# SensorManagementSystem.net
KiCad netlist of a schematic drawn in Altium Designer
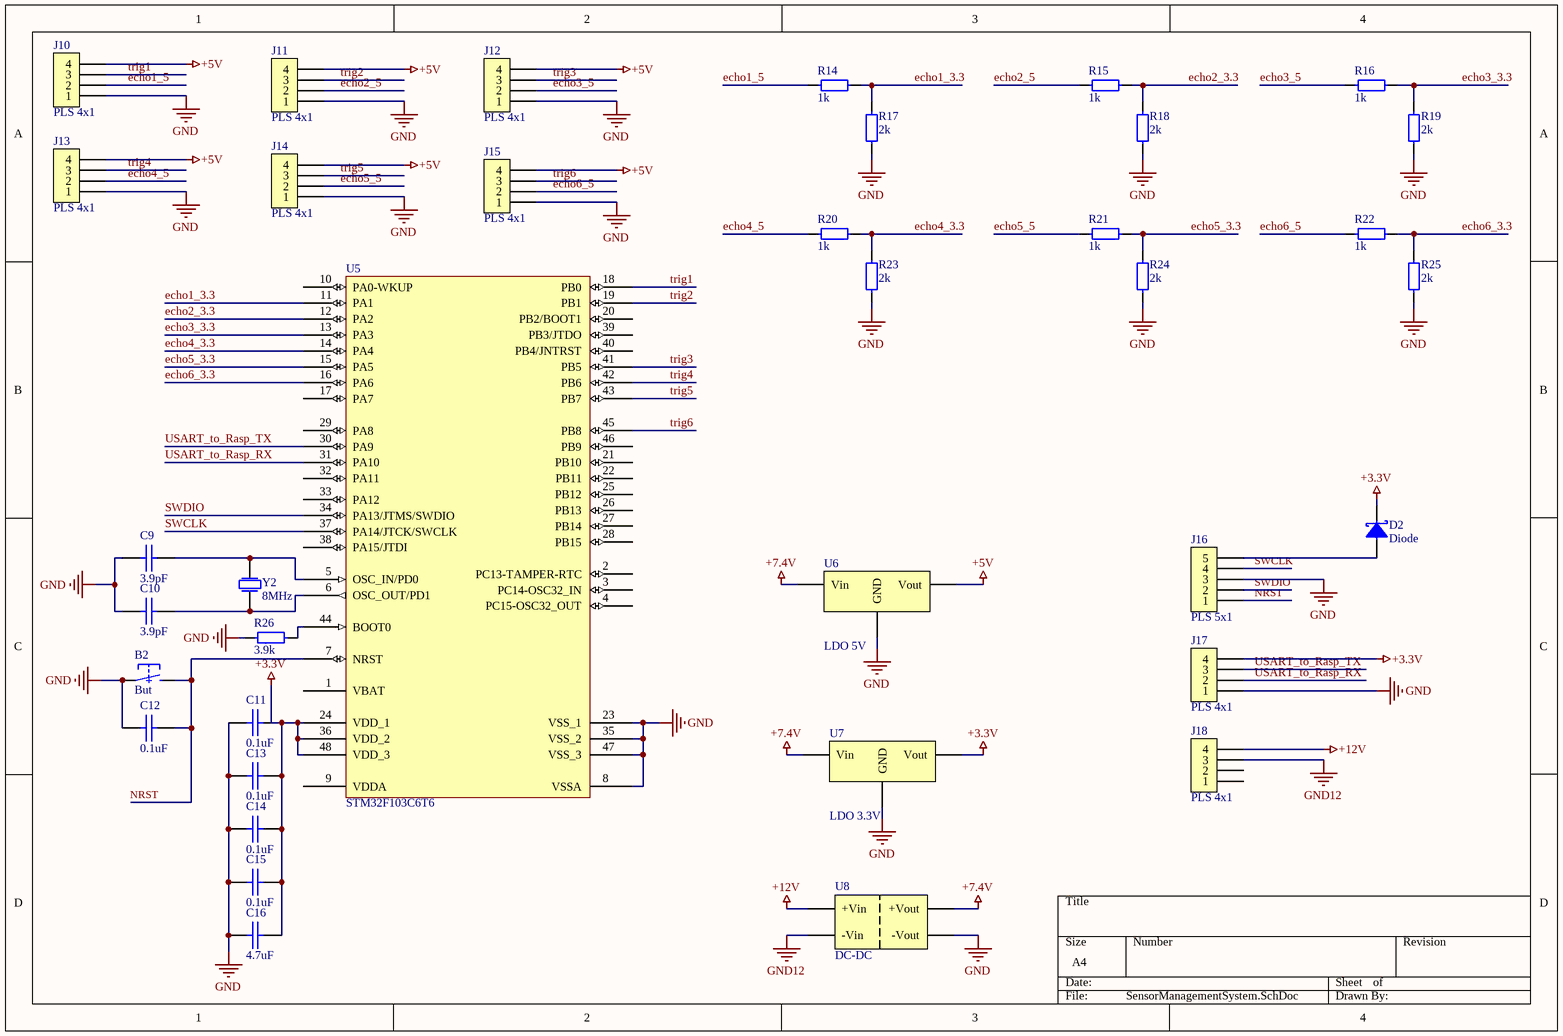
[diagram p0: SensorManagementSystem.SchDoc]

(export (version "E")
  (design (tool "Eeschema 10.0.6"))
  (components
    (comp (ref "B2")
      (value "But")
      (footprint "BUTTON 6x3.5")
      (description "Button 2 Conn SMD")
      (libsource (lib "RoboCor") (part "Button"))
    )
    (comp (ref "C9")
      (value "3.9pF")
      (footprint "0805 Capicator")
      (libsource (lib "RoboCor") (part "Cap 39pF"))
    )
    (comp (ref "C10")
      (value "3.9pF")
      (footprint "0805 Capicator")
      (libsource (lib "RoboCor") (part "Cap 39pF"))
    )
    (comp (ref "C11")
      (value "0.1uF")
      (footprint "0805 Capicator")
      (libsource (lib "RoboCor") (part "Cap 0.1uF"))
    )
    (comp (ref "C12")
      (value "0.1uF")
      (footprint "0805 Capicator")
      (libsource (lib "RoboCor") (part "Cap 0.1uF"))
    )
    (comp (ref "C13")
      (value "0.1uF")
      (footprint "0805 Capicator")
      (libsource (lib "RoboCor") (part "Cap 0.1uF"))
    )
    (comp (ref "C14")
      (value "0.1uF")
      (footprint "0805 Capicator")
      (libsource (lib "RoboCor") (part "Cap 0.1uF"))
    )
    (comp (ref "C15")
      (value "0.1uF")
      (footprint "0805 Capicator")
      (libsource (lib "RoboCor") (part "Cap 0.1uF"))
    )
    (comp (ref "C16")
      (value "4.7uF")
      (footprint "0805 Capicator")
      (libsource (lib "RoboCor") (part "Cap 4.7uF"))
    )
    (comp (ref "D2")
      (value "Diode")
      (footprint "sod-123")
      (description "0.5 A, Low Forward Voltage less than 385 mV, 400 mW Power Dissipation Package")
      (libsource (lib "RoboCor") (part "Diode Schottky"))
    )
    (comp (ref "J10")
      (value "PLS 4x1")
      (footprint "PLS 4x1")
      (description "Header, 4-Pin")
      (libsource (lib "RoboCor") (part "Conn 4"))
    )
    (comp (ref "J11")
      (value "PLS 4x1")
      (footprint "PLS 4x1")
      (description "Header, 4-Pin")
      (libsource (lib "RoboCor") (part "Conn 4"))
    )
    (comp (ref "J12")
      (value "PLS 4x1")
      (footprint "PLS 4x1")
      (description "Header, 4-Pin")
      (libsource (lib "RoboCor") (part "Conn 4"))
    )
    (comp (ref "J13")
      (value "PLS 4x1")
      (footprint "PLS 4x1")
      (description "Header, 4-Pin")
      (libsource (lib "RoboCor") (part "Conn 4"))
    )
    (comp (ref "J14")
      (value "PLS 4x1")
      (footprint "PLS 4x1")
      (description "Header, 4-Pin")
      (libsource (lib "RoboCor") (part "Conn 4"))
    )
    (comp (ref "J15")
      (value "PLS 4x1")
      (footprint "PLS 4x1")
      (description "Header, 4-Pin")
      (libsource (lib "RoboCor") (part "Conn 4"))
    )
    (comp (ref "J16")
      (value "PLS 5x1")
      (footprint "PLS 5x1")
      (description "Header, 5-Pin")
      (libsource (lib "RoboCor") (part "Conn 5"))
    )
    (comp (ref "J17")
      (value "PLS 4x1")
      (footprint "PLS 4x1")
      (description "Header, 4-Pin")
      (libsource (lib "RoboCor") (part "Conn 4"))
    )
    (comp (ref "J18")
      (value "PLS 4x1")
      (footprint "PLS 4x1")
      (description "Header, 4-Pin")
      (libsource (lib "RoboCor") (part "Conn 4"))
    )
    (comp (ref "R14") (value "1k") (footprint "0805 Resistor") (libsource (lib "RoboCor") (part "Res 1k")))
    (comp (ref "R15") (value "1k") (footprint "0805 Resistor") (libsource (lib "RoboCor") (part "Res 1k")))
    (comp (ref "R16") (value "1k") (footprint "0805 Resistor") (libsource (lib "RoboCor") (part "Res 1k")))
    (comp (ref "R17") (value "2k") (footprint "0805 Resistor") (libsource (lib "RoboCor") (part "Res 2k")))
    (comp (ref "R18") (value "2k") (footprint "0805 Resistor") (libsource (lib "RoboCor") (part "Res 2k")))
    (comp (ref "R19") (value "2k") (footprint "0805 Resistor") (libsource (lib "RoboCor") (part "Res 2k")))
    (comp (ref "R20") (value "1k") (footprint "0805 Resistor") (libsource (lib "RoboCor") (part "Res 1k")))
    (comp (ref "R21") (value "1k") (footprint "0805 Resistor") (libsource (lib "RoboCor") (part "Res 1k")))
    (comp (ref "R22") (value "1k") (footprint "0805 Resistor") (libsource (lib "RoboCor") (part "Res 1k")))
    (comp (ref "R23") (value "2k") (footprint "0805 Resistor") (libsource (lib "RoboCor") (part "Res 2k")))
    (comp (ref "R24") (value "2k") (footprint "0805 Resistor") (libsource (lib "RoboCor") (part "Res 2k")))
    (comp (ref "R25") (value "2k") (footprint "0805 Resistor") (libsource (lib "RoboCor") (part "Res 2k")))
    (comp (ref "R26")
      (value "3.9k")
      (footprint "0805 Resistor")
      (libsource (lib "RoboCor") (part "Res 3.9k"))
    )
    (comp (ref "U5")
      (value "STM32F103C6T6")
      (footprint "STM32F103C6T6")
      (libsource (lib "RoboCor") (part "STM32F103C6T6"))
    )
    (comp (ref "U6")
      (value "LDO 5V")
      (footprint "TO-252")
      (description "LDO Regulator Pos 5V 1A")
      (libsource (lib "RoboCor") (part "LDO 5V"))
    )
    (comp (ref "U7")
      (value "LDO 3.3V")
      (footprint "SOT-223")
      (description "LDO Regulator Pos 3.3V 1.3A 4-Pin(3+Tab) SOT-223 T/R")
      (libsource (lib "RoboCor") (part "LDO 3.3V"))
    )
    (comp (ref "U8") (value "DC-DC") (footprint "DC-DC") (libsource (lib "RoboCor") (part "DC-DC")))
    (comp (ref "Y2")
      (value "8MHz")
      (footprint "hc-49sm")
      (description "Crystal. HC-49SM (US)")
      (libsource (lib "RoboCor") (part "Crystal 8MHz"))
    )
  )
  (nets
    (net (code "1") (name "+3.3V") (class "Default")
      (node (ref "C11") (pin "2") (pinfunction "2_2") (pintype "passive"))
      (node (ref "C13") (pin "2") (pinfunction "2_2") (pintype "passive"))
      (node (ref "C14") (pin "2") (pinfunction "2_2") (pintype "passive"))
      (node (ref "C15") (pin "2") (pinfunction "2_2") (pintype "passive"))
      (node (ref "C16") (pin "2") (pinfunction "2_2") (pintype "passive"))
      (node (ref "D2") (pin "2") (pinfunction "2_2") (pintype "passive"))
      (node (ref "J17") (pin "4") (pinfunction "4_4") (pintype "passive"))
      (node (ref "U5") (pin "24") (pinfunction "VDD_1_24") (pintype "power_in"))
      (node (ref "U5") (pin "36") (pinfunction "VDD_2_36") (pintype "power_in"))
      (node (ref "U5") (pin "48") (pinfunction "VDD_3_48") (pintype "power_in"))
      (node (ref "U7") (pin "2") (pinfunction "Vout_2") (pintype "power_in"))
    )
    (net (code "2") (name "+5V") (class "Default")
      (node (ref "J10") (pin "4") (pinfunction "4_4") (pintype "passive"))
      (node (ref "J11") (pin "4") (pinfunction "4_4") (pintype "passive"))
      (node (ref "J12") (pin "4") (pinfunction "4_4") (pintype "passive"))
      (node (ref "J13") (pin "4") (pinfunction "4_4") (pintype "passive"))
      (node (ref "J14") (pin "4") (pinfunction "4_4") (pintype "passive"))
      (node (ref "J15") (pin "4") (pinfunction "4_4") (pintype "passive"))
      (node (ref "U6") (pin "2") (pinfunction "Vout_2") (pintype "power_in"))
    )
    (net (code "3") (name "+7.4V") (class "Default")
      (node (ref "U6") (pin "3") (pinfunction "Vin_3") (pintype "power_in"))
      (node (ref "U7") (pin "3") (pinfunction "Vin_3") (pintype "power_in"))
      (node (ref "U8") (pin "3") (pinfunction "+Vout_3") (pintype "power_in"))
    )
    (net (code "4") (name "+12V") (class "Default")
      (node (ref "J18") (pin "4") (pinfunction "4_4") (pintype "passive"))
      (node (ref "U8") (pin "1") (pinfunction "+Vin_1") (pintype "power_in"))
    )
    (net (code "5") (name "/NRST") (class "Default")
      (node (ref "B2") (pin "2") (pinfunction "2_2") (pintype "passive"))
      (node (ref "C12") (pin "2") (pinfunction "2_2") (pintype "passive"))
      (node (ref "J16") (pin "1") (pinfunction "1_1") (pintype "passive"))
      (node (ref "U5") (pin "7") (pinfunction "NRST_7") (pintype "bidirectional"))
    )
    (net (code "6") (name "/SWCLK") (class "Default")
      (node (ref "J16") (pin "4") (pinfunction "4_4") (pintype "passive"))
      (node (ref "U5") (pin "37") (pinfunction "PA14/JTCK/SWCLK_37") (pintype "bidirectional"))
    )
    (net (code "7") (name "/SWDIO") (class "Default")
      (node (ref "J16") (pin "2") (pinfunction "2_2") (pintype "passive"))
      (node (ref "U5") (pin "34") (pinfunction "PA13/JTMS/SWDIO_34") (pintype "bidirectional"))
    )
    (net (code "8") (name "/USART_to_Rasp_RX") (class "Default")
      (node (ref "J17") (pin "2") (pinfunction "2_2") (pintype "passive"))
      (node (ref "U5") (pin "31") (pinfunction "PA10_31") (pintype "bidirectional"))
    )
    (net (code "9") (name "/USART_to_Rasp_TX") (class "Default")
      (node (ref "J17") (pin "3") (pinfunction "3_3") (pintype "passive"))
      (node (ref "U5") (pin "30") (pinfunction "PA9_30") (pintype "bidirectional"))
    )
    (net (code "10") (name "/echo1_3.3") (class "Default")
      (node (ref "R14") (pin "2") (pinfunction "2_2") (pintype "passive"))
      (node (ref "R17") (pin "2") (pinfunction "2_2") (pintype "passive"))
      (node (ref "U5") (pin "11") (pinfunction "PA1_11") (pintype "bidirectional"))
    )
    (net (code "11") (name "/echo1_5") (class "Default")
      (node (ref "J10") (pin "2") (pinfunction "2_2") (pintype "passive"))
      (node (ref "R14") (pin "1") (pinfunction "1_1") (pintype "passive"))
    )
    (net (code "12") (name "/echo2_3.3") (class "Default")
      (node (ref "R15") (pin "2") (pinfunction "2_2") (pintype "passive"))
      (node (ref "R18") (pin "2") (pinfunction "2_2") (pintype "passive"))
      (node (ref "U5") (pin "12") (pinfunction "PA2_12") (pintype "bidirectional"))
    )
    (net (code "13") (name "/echo2_5") (class "Default")
      (node (ref "J11") (pin "2") (pinfunction "2_2") (pintype "passive"))
      (node (ref "R15") (pin "1") (pinfunction "1_1") (pintype "passive"))
    )
    (net (code "14") (name "/echo3_3.3") (class "Default")
      (node (ref "R16") (pin "2") (pinfunction "2_2") (pintype "passive"))
      (node (ref "R19") (pin "2") (pinfunction "2_2") (pintype "passive"))
      (node (ref "U5") (pin "13") (pinfunction "PA3_13") (pintype "bidirectional"))
    )
    (net (code "15") (name "/echo3_5") (class "Default")
      (node (ref "J12") (pin "2") (pinfunction "2_2") (pintype "passive"))
      (node (ref "R16") (pin "1") (pinfunction "1_1") (pintype "passive"))
    )
    (net (code "16") (name "/echo4_3.3") (class "Default")
      (node (ref "R20") (pin "2") (pinfunction "2_2") (pintype "passive"))
      (node (ref "R23") (pin "2") (pinfunction "2_2") (pintype "passive"))
      (node (ref "U5") (pin "14") (pinfunction "PA4_14") (pintype "bidirectional"))
    )
    (net (code "17") (name "/echo4_5") (class "Default")
      (node (ref "J13") (pin "2") (pinfunction "2_2") (pintype "passive"))
      (node (ref "R20") (pin "1") (pinfunction "1_1") (pintype "passive"))
    )
    (net (code "18") (name "/echo5_3.3") (class "Default")
      (node (ref "R21") (pin "2") (pinfunction "2_2") (pintype "passive"))
      (node (ref "R24") (pin "2") (pinfunction "2_2") (pintype "passive"))
      (node (ref "U5") (pin "15") (pinfunction "PA5_15") (pintype "bidirectional"))
    )
    (net (code "19") (name "/echo5_5") (class "Default")
      (node (ref "J14") (pin "2") (pinfunction "2_2") (pintype "passive"))
      (node (ref "R21") (pin "1") (pinfunction "1_1") (pintype "passive"))
    )
    (net (code "20") (name "/echo6_3.3") (class "Default")
      (node (ref "R22") (pin "2") (pinfunction "2_2") (pintype "passive"))
      (node (ref "R25") (pin "2") (pinfunction "2_2") (pintype "passive"))
      (node (ref "U5") (pin "16") (pinfunction "PA6_16") (pintype "bidirectional"))
    )
    (net (code "21") (name "/echo6_5") (class "Default")
      (node (ref "J15") (pin "2") (pinfunction "2_2") (pintype "passive"))
      (node (ref "R22") (pin "1") (pinfunction "1_1") (pintype "passive"))
    )
    (net (code "22") (name "/trig1") (class "Default")
      (node (ref "J10") (pin "3") (pinfunction "3_3") (pintype "passive"))
      (node (ref "U5") (pin "18") (pinfunction "PB0_18") (pintype "bidirectional"))
    )
    (net (code "23") (name "/trig2") (class "Default")
      (node (ref "J11") (pin "3") (pinfunction "3_3") (pintype "passive"))
      (node (ref "U5") (pin "19") (pinfunction "PB1_19") (pintype "bidirectional"))
    )
    (net (code "24") (name "/trig3") (class "Default")
      (node (ref "J12") (pin "3") (pinfunction "3_3") (pintype "passive"))
      (node (ref "U5") (pin "41") (pinfunction "PB5_41") (pintype "bidirectional"))
    )
    (net (code "25") (name "/trig4") (class "Default")
      (node (ref "J13") (pin "3") (pinfunction "3_3") (pintype "passive"))
      (node (ref "U5") (pin "42") (pinfunction "PB6_42") (pintype "bidirectional"))
    )
    (net (code "26") (name "/trig5") (class "Default")
      (node (ref "J14") (pin "3") (pinfunction "3_3") (pintype "passive"))
      (node (ref "U5") (pin "43") (pinfunction "PB7_43") (pintype "bidirectional"))
    )
    (net (code "27") (name "/trig6") (class "Default")
      (node (ref "J15") (pin "3") (pinfunction "3_3") (pintype "passive"))
      (node (ref "U5") (pin "45") (pinfunction "PB8_45") (pintype "bidirectional"))
    )
    (net (code "28") (name "GND") (class "Default")
      (node (ref "B2") (pin "1") (pinfunction "1_1") (pintype "passive"))
      (node (ref "C10") (pin "1") (pinfunction "1_1") (pintype "passive"))
      (node (ref "C11") (pin "1") (pinfunction "1_1") (pintype "passive"))
      (node (ref "C12") (pin "1") (pinfunction "1_1") (pintype "passive"))
      (node (ref "C13") (pin "1") (pinfunction "1_1") (pintype "passive"))
      (node (ref "C14") (pin "1") (pinfunction "1_1") (pintype "passive"))
      (node (ref "C15") (pin "1") (pinfunction "1_1") (pintype "passive"))
      (node (ref "C16") (pin "1") (pinfunction "1_1") (pintype "passive"))
      (node (ref "C9") (pin "1") (pinfunction "1_1") (pintype "passive"))
      (node (ref "J10") (pin "1") (pinfunction "1_1") (pintype "passive"))
      (node (ref "J11") (pin "1") (pinfunction "1_1") (pintype "passive"))
      (node (ref "J12") (pin "1") (pinfunction "1_1") (pintype "passive"))
      (node (ref "J13") (pin "1") (pinfunction "1_1") (pintype "passive"))
      (node (ref "J14") (pin "1") (pinfunction "1_1") (pintype "passive"))
      (node (ref "J15") (pin "1") (pinfunction "1_1") (pintype "passive"))
      (node (ref "J16") (pin "3") (pinfunction "3_3") (pintype "passive"))
      (node (ref "J17") (pin "1") (pinfunction "1_1") (pintype "passive"))
      (node (ref "R17") (pin "1") (pinfunction "1_1") (pintype "passive"))
      (node (ref "R18") (pin "1") (pinfunction "1_1") (pintype "passive"))
      (node (ref "R19") (pin "1") (pinfunction "1_1") (pintype "passive"))
      (node (ref "R23") (pin "1") (pinfunction "1_1") (pintype "passive"))
      (node (ref "R24") (pin "1") (pinfunction "1_1") (pintype "passive"))
      (node (ref "R25") (pin "1") (pinfunction "1_1") (pintype "passive"))
      (node (ref "R26") (pin "1") (pinfunction "1_1") (pintype "passive"))
      (node (ref "U5") (pin "23") (pinfunction "VSS_1_23") (pintype "power_in"))
      (node (ref "U5") (pin "35") (pinfunction "VSS_2_35") (pintype "power_in"))
      (node (ref "U5") (pin "47") (pinfunction "VSS_3_47") (pintype "power_in"))
      (node (ref "U5") (pin "8") (pinfunction "VSSA_8") (pintype "power_in"))
      (node (ref "U6") (pin "1") (pinfunction "GND_1") (pintype "power_in"))
      (node (ref "U7") (pin "1") (pinfunction "GND_1") (pintype "power_in"))
      (node (ref "U8") (pin "4") (pinfunction "-Vout_4") (pintype "power_in"))
    )
    (net (code "29") (name "GND12") (class "Default")
      (node (ref "J18") (pin "3") (pinfunction "3_3") (pintype "passive"))
      (node (ref "U8") (pin "2") (pinfunction "-Vin_2") (pintype "power_in"))
    )
    (net (code "30") (name "Net-(D2-Pad1)") (class "Default")
      (node (ref "D2") (pin "1") (pinfunction "1_1") (pintype "passive"))
      (node (ref "J16") (pin "5") (pinfunction "5_5") (pintype "passive"))
    )
    (net (code "31") (name "Net-(U5-BOOT0)") (class "Default")
      (node (ref "R26") (pin "2") (pinfunction "2_2") (pintype "passive"))
      (node (ref "U5") (pin "44") (pinfunction "BOOT0_44") (pintype "input"))
    )
    (net (code "32") (name "Net-(U5-OSC_IN{slash}PD0)") (class "Default")
      (node (ref "C9") (pin "2") (pinfunction "2_2") (pintype "passive"))
      (node (ref "U5") (pin "5") (pinfunction "OSC_IN/PD0_5") (pintype "input"))
      (node (ref "Y2") (pin "2") (pinfunction "2_2") (pintype "passive"))
    )
    (net (code "33") (name "Net-(U5-OSC_OUT{slash}PD1)") (class "Default")
      (node (ref "C10") (pin "2") (pinfunction "2_2") (pintype "passive"))
      (node (ref "U5") (pin "6") (pinfunction "OSC_OUT/PD1_6") (pintype "output"))
      (node (ref "Y2") (pin "1") (pinfunction "1_1") (pintype "passive"))
    )
    (net (code "34") (name "unconnected-(J18-Pad1)") (class "Default")
      (node (ref "J18") (pin "1") (pinfunction "1_1") (pintype "passive"))
    )
    (net (code "35") (name "unconnected-(J18-Pad2)") (class "Default")
      (node (ref "J18") (pin "2") (pinfunction "2_2") (pintype "passive"))
    )
    (net (code "36") (name "unconnected-(U5-PA0-WKUP-Pad10)") (class "Default")
      (node (ref "U5") (pin "10") (pinfunction "PA0-WKUP_10") (pintype "bidirectional"))
    )
    (net (code "37") (name "unconnected-(U5-PA7-Pad17)") (class "Default")
      (node (ref "U5") (pin "17") (pinfunction "PA7_17") (pintype "bidirectional"))
    )
    (net (code "38") (name "unconnected-(U5-PA8-Pad29)") (class "Default")
      (node (ref "U5") (pin "29") (pinfunction "PA8_29") (pintype "bidirectional"))
    )
    (net (code "39") (name "unconnected-(U5-PA11-Pad32)") (class "Default")
      (node (ref "U5") (pin "32") (pinfunction "PA11_32") (pintype "bidirectional"))
    )
    (net (code "40") (name "unconnected-(U5-PA12-Pad33)") (class "Default")
      (node (ref "U5") (pin "33") (pinfunction "PA12_33") (pintype "bidirectional"))
    )
    (net (code "41") (name "unconnected-(U5-PA15{slash}JTDI-Pad38)") (class "Default")
      (node (ref "U5") (pin "38") (pinfunction "PA15/JTDI_38") (pintype "bidirectional"))
    )
    (net (code "42") (name "unconnected-(U5-PB2{slash}BOOT1-Pad20)") (class "Default")
      (node (ref "U5") (pin "20") (pinfunction "PB2/BOOT1_20") (pintype "bidirectional"))
    )
    (net (code "43") (name "unconnected-(U5-PB3{slash}JTDO-Pad39)") (class "Default")
      (node (ref "U5") (pin "39") (pinfunction "PB3/JTDO_39") (pintype "bidirectional"))
    )
    (net (code "44") (name "unconnected-(U5-PB4{slash}JNTRST-Pad40)") (class "Default")
      (node (ref "U5") (pin "40") (pinfunction "PB4/JNTRST_40") (pintype "bidirectional"))
    )
    (net (code "45") (name "unconnected-(U5-PB9-Pad46)") (class "Default")
      (node (ref "U5") (pin "46") (pinfunction "PB9_46") (pintype "bidirectional"))
    )
    (net (code "46") (name "unconnected-(U5-PB10-Pad21)") (class "Default")
      (node (ref "U5") (pin "21") (pinfunction "PB10_21") (pintype "bidirectional"))
    )
    (net (code "47") (name "unconnected-(U5-PB11-Pad22)") (class "Default")
      (node (ref "U5") (pin "22") (pinfunction "PB11_22") (pintype "bidirectional"))
    )
    (net (code "48") (name "unconnected-(U5-PB12-Pad25)") (class "Default")
      (node (ref "U5") (pin "25") (pinfunction "PB12_25") (pintype "bidirectional"))
    )
    (net (code "49") (name "unconnected-(U5-PB13-Pad26)") (class "Default")
      (node (ref "U5") (pin "26") (pinfunction "PB13_26") (pintype "bidirectional"))
    )
    (net (code "50") (name "unconnected-(U5-PB14-Pad27)") (class "Default")
      (node (ref "U5") (pin "27") (pinfunction "PB14_27") (pintype "bidirectional"))
    )
    (net (code "51") (name "unconnected-(U5-PB15-Pad28)") (class "Default")
      (node (ref "U5") (pin "28") (pinfunction "PB15_28") (pintype "bidirectional"))
    )
    (net (code "52") (name "unconnected-(U5-PC13-TAMPER-RTC-Pad2)") (class "Default")
      (node (ref "U5") (pin "2") (pinfunction "PC13-TAMPER-RTC_2") (pintype "bidirectional"))
    )
    (net (code "53") (name "unconnected-(U5-PC14-OSC32_IN-Pad3)") (class "Default")
      (node (ref "U5") (pin "3") (pinfunction "PC14-OSC32_IN_3") (pintype "bidirectional"))
    )
    (net (code "54") (name "unconnected-(U5-PC15-OSC32_OUT-Pad4)") (class "Default")
      (node (ref "U5") (pin "4") (pinfunction "PC15-OSC32_OUT_4") (pintype "bidirectional"))
    )
    (net (code "55") (name "unconnected-(U5-VBAT-Pad1)") (class "Default")
      (node (ref "U5") (pin "1") (pinfunction "VBAT_1") (pintype "power_in"))
    )
    (net (code "56") (name "unconnected-(U5-VDDA-Pad9)") (class "Default")
      (node (ref "U5") (pin "9") (pinfunction "VDDA_9") (pintype "power_in"))
    )
  )
)
